# Mainboard_V1_0_HMI.net
KiCad netlist of a schematic drawn in Altium Designer
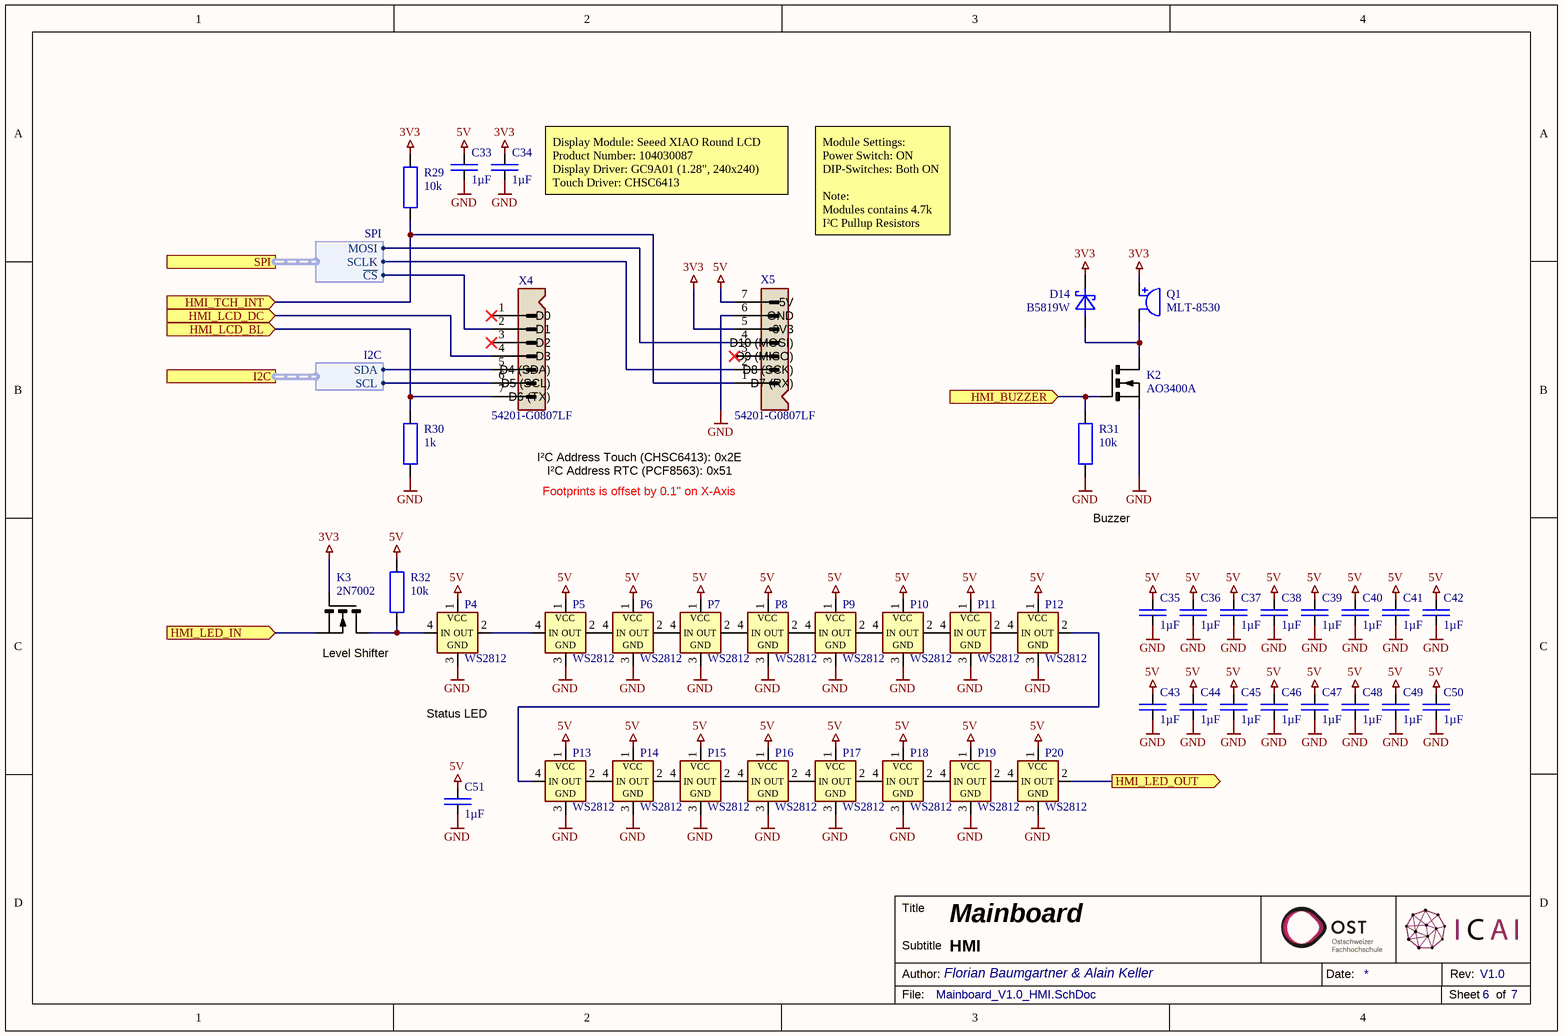
[diagram p0: Mainboard_V1.0_HMI.SchDoc]

(export (version "E")
  (design (tool "Eeschema 10.0.6"))
  (components
    (comp (ref "C33")
      (value "1µF")
      (footprint "SMD Keramikkondensator 0603")
      (description "CAP-MK")
      (libsource (lib "AudioAmp") (part "C-CAPACITOR"))
    )
    (comp (ref "C34")
      (value "1µF")
      (footprint "SMD Keramikkondensator 0603")
      (description "CAP-MK")
      (libsource (lib "AudioAmp") (part "C-CAPACITOR"))
    )
    (comp (ref "C35")
      (value "1µF")
      (footprint "SMD Keramikkondensator 0603")
      (description "CAP-MK")
      (libsource (lib "AudioAmp") (part "C-CAPACITOR"))
    )
    (comp (ref "C36")
      (value "1µF")
      (footprint "SMD Keramikkondensator 0603")
      (description "CAP-MK")
      (libsource (lib "AudioAmp") (part "C-CAPACITOR"))
    )
    (comp (ref "C37")
      (value "1µF")
      (footprint "SMD Keramikkondensator 0603")
      (description "CAP-MK")
      (libsource (lib "AudioAmp") (part "C-CAPACITOR"))
    )
    (comp (ref "C38")
      (value "1µF")
      (footprint "SMD Keramikkondensator 0603")
      (description "CAP-MK")
      (libsource (lib "AudioAmp") (part "C-CAPACITOR"))
    )
    (comp (ref "C39")
      (value "1µF")
      (footprint "SMD Keramikkondensator 0603")
      (description "CAP-MK")
      (libsource (lib "AudioAmp") (part "C-CAPACITOR"))
    )
    (comp (ref "C40")
      (value "1µF")
      (footprint "SMD Keramikkondensator 0603")
      (description "CAP-MK")
      (libsource (lib "AudioAmp") (part "C-CAPACITOR"))
    )
    (comp (ref "C41")
      (value "1µF")
      (footprint "SMD Keramikkondensator 0603")
      (description "CAP-MK")
      (libsource (lib "AudioAmp") (part "C-CAPACITOR"))
    )
    (comp (ref "C42")
      (value "1µF")
      (footprint "SMD Keramikkondensator 0603")
      (description "CAP-MK")
      (libsource (lib "AudioAmp") (part "C-CAPACITOR"))
    )
    (comp (ref "C43")
      (value "1µF")
      (footprint "SMD Keramikkondensator 0603")
      (description "CAP-MK")
      (libsource (lib "AudioAmp") (part "C-CAPACITOR"))
    )
    (comp (ref "C44")
      (value "1µF")
      (footprint "SMD Keramikkondensator 0603")
      (description "CAP-MK")
      (libsource (lib "AudioAmp") (part "C-CAPACITOR"))
    )
    (comp (ref "C45")
      (value "1µF")
      (footprint "SMD Keramikkondensator 0603")
      (description "CAP-MK")
      (libsource (lib "AudioAmp") (part "C-CAPACITOR"))
    )
    (comp (ref "C46")
      (value "1µF")
      (footprint "SMD Keramikkondensator 0603")
      (description "CAP-MK")
      (libsource (lib "AudioAmp") (part "C-CAPACITOR"))
    )
    (comp (ref "C47")
      (value "1µF")
      (footprint "SMD Keramikkondensator 0603")
      (description "CAP-MK")
      (libsource (lib "AudioAmp") (part "C-CAPACITOR"))
    )
    (comp (ref "C48")
      (value "1µF")
      (footprint "SMD Keramikkondensator 0603")
      (description "CAP-MK")
      (libsource (lib "AudioAmp") (part "C-CAPACITOR"))
    )
    (comp (ref "C49")
      (value "1µF")
      (footprint "SMD Keramikkondensator 0603")
      (description "CAP-MK")
      (libsource (lib "AudioAmp") (part "C-CAPACITOR"))
    )
    (comp (ref "C50")
      (value "1µF")
      (footprint "SMD Keramikkondensator 0603")
      (description "CAP-MK")
      (libsource (lib "AudioAmp") (part "C-CAPACITOR"))
    )
    (comp (ref "C51")
      (value "1µF")
      (footprint "SMD Keramikkondensator 0603")
      (description "CAP-MK")
      (libsource (lib "AudioAmp") (part "C-CAPACITOR"))
    )
    (comp (ref "D14")
      (value "B5819W")
      (footprint "SMD Diode SOD-123")
      (description "S-DIODE")
      (libsource (lib "TFS Integrated Library") (part "R-DIODE{colon}SCHKY"))
    )
    (comp (ref "K2")
      (value "AO3400A")
      (footprint "SMD MOSFET SOT-23")
      (description "MOSFET N-Channel")
      (libsource (lib "") (part "K-FET{colon}NIGE_1"))
    )
    (comp (ref "K3")
      (value "2N7002")
      (footprint "SMD MOSFET SOT-23")
      (description "MOSFET N-Channel")
      (libsource (lib "Nixie-Test") (part "K-FET{colon}NIGE"))
    )
    (comp (ref "P4")
      (value "WS2812")
      (footprint "SMD LED WS2812B-0807")
      (description "Smart RGB-LED")
      (libsource (lib "Acquisition-System") (part "P-WS2812B-0807"))
    )
    (comp (ref "P5")
      (value "WS2812")
      (footprint "SMD LED WS2812B-0807")
      (description "Smart RGB-LED")
      (libsource (lib "Acquisition-System") (part "P-WS2812B-0807"))
    )
    (comp (ref "P6")
      (value "WS2812")
      (footprint "SMD LED WS2812B-0807")
      (description "Smart RGB-LED")
      (libsource (lib "Acquisition-System") (part "P-WS2812B-0807"))
    )
    (comp (ref "P7")
      (value "WS2812")
      (footprint "SMD LED WS2812B-0807")
      (description "Smart RGB-LED")
      (libsource (lib "Acquisition-System") (part "P-WS2812B-0807"))
    )
    (comp (ref "P8")
      (value "WS2812")
      (footprint "SMD LED WS2812B-0807")
      (description "Smart RGB-LED")
      (libsource (lib "Acquisition-System") (part "P-WS2812B-0807"))
    )
    (comp (ref "P9")
      (value "WS2812")
      (footprint "SMD LED WS2812B-0807")
      (description "Smart RGB-LED")
      (libsource (lib "Acquisition-System") (part "P-WS2812B-0807"))
    )
    (comp (ref "P10")
      (value "WS2812")
      (footprint "SMD LED WS2812B-0807")
      (description "Smart RGB-LED")
      (libsource (lib "Acquisition-System") (part "P-WS2812B-0807"))
    )
    (comp (ref "P11")
      (value "WS2812")
      (footprint "SMD LED WS2812B-0807")
      (description "Smart RGB-LED")
      (libsource (lib "Acquisition-System") (part "P-WS2812B-0807"))
    )
    (comp (ref "P12")
      (value "WS2812")
      (footprint "SMD LED WS2812B-0807")
      (description "Smart RGB-LED")
      (libsource (lib "Acquisition-System") (part "P-WS2812B-0807"))
    )
    (comp (ref "P13")
      (value "WS2812")
      (footprint "SMD LED WS2812B-0807")
      (description "Smart RGB-LED")
      (libsource (lib "Acquisition-System") (part "P-WS2812B-0807"))
    )
    (comp (ref "P14")
      (value "WS2812")
      (footprint "SMD LED WS2812B-0807")
      (description "Smart RGB-LED")
      (libsource (lib "Acquisition-System") (part "P-WS2812B-0807"))
    )
    (comp (ref "P15")
      (value "WS2812")
      (footprint "SMD LED WS2812B-0807")
      (description "Smart RGB-LED")
      (libsource (lib "Acquisition-System") (part "P-WS2812B-0807"))
    )
    (comp (ref "P16")
      (value "WS2812")
      (footprint "SMD LED WS2812B-0807")
      (description "Smart RGB-LED")
      (libsource (lib "Acquisition-System") (part "P-WS2812B-0807"))
    )
    (comp (ref "P17")
      (value "WS2812")
      (footprint "SMD LED WS2812B-0807")
      (description "Smart RGB-LED")
      (libsource (lib "Acquisition-System") (part "P-WS2812B-0807"))
    )
    (comp (ref "P18")
      (value "WS2812")
      (footprint "SMD LED WS2812B-0807")
      (description "Smart RGB-LED")
      (libsource (lib "Acquisition-System") (part "P-WS2812B-0807"))
    )
    (comp (ref "P19")
      (value "WS2812")
      (footprint "SMD LED WS2812B-0807")
      (description "Smart RGB-LED")
      (libsource (lib "Acquisition-System") (part "P-WS2812B-0807"))
    )
    (comp (ref "P20")
      (value "WS2812")
      (footprint "SMD LED WS2812B-0807")
      (description "Smart RGB-LED")
      (libsource (lib "Acquisition-System") (part "P-WS2812B-0807"))
    )
    (comp (ref "Q1")
      (value "MLT-8530")
      (footprint "SMD Buzzer (MLT-8530)")
      (description "Electromagnetic Buzzer")
      (libsource (lib "Velotour_2022") (part "Q-Buzzer"))
    )
    (comp (ref "R29")
      (value "10k")
      (footprint "SMD Widerstand 0603")
      (description "RES (E=Heizwiderstand B=Messwandler)")
      (libsource (lib "TFS Integrated Library") (part "R-RESISTOR"))
    )
    (comp (ref "R30")
      (value "1k")
      (footprint "SMD Widerstand 0603")
      (description "RES (E=Heizwiderstand B=Messwandler)")
      (libsource (lib "TFS Integrated Library") (part "R-RESISTOR"))
    )
    (comp (ref "R31")
      (value "10k")
      (footprint "SMD Widerstand 0603")
      (description "RES (E=Heizwiderstand B=Messwandler)")
      (libsource (lib "TFS Integrated Library") (part "R-RESISTOR"))
    )
    (comp (ref "R32")
      (value "10k")
      (footprint "SMD Widerstand 0603")
      (description "RES (E=Heizwiderstand B=Messwandler)")
      (libsource (lib "TFS Integrated Library") (part "R-RESISTOR"))
    )
    (comp (ref "X4")
      (value "54201-G0807LF")
      (footprint "SMD Pin-Header 1x7")
      (libsource (lib "Mainboard") (part "X-Stiftleiste (7-Fach)"))
    )
    (comp (ref "X5")
      (value "54201-G0807LF")
      (footprint "SMD Pin-Header 1x7")
      (libsource (lib "") (part "X-Stiftleiste (7-Fach)_1"))
    )
  )
  (nets
    (net (code "3") (name "/HMI_BUZZER") (class "Default")
      (node (ref "K2") (pin "G") (pinfunction "G_G") (pintype "passive"))
      (node (ref "R31") (pin "2") (pinfunction "2_2") (pintype "passive"))
    )
    (net (code "4") (name "/HMI_LCD_BL") (class "Default")
      (node (ref "R30") (pin "2") (pinfunction "2_2") (pintype "passive"))
      (node (ref "X4") (pin "7") (pinfunction "7_7") (pintype "passive"))
    )
    (net (code "5") (name "/HMI_LCD_DC") (class "Default")
      (node (ref "X4") (pin "4") (pinfunction "4_4") (pintype "passive"))
    )
    (net (code "6") (name "/HMI_LED_IN") (class "Default")
      (node (ref "K3") (pin "S") (pinfunction "S_S") (pintype "passive"))
    )
    (net (code "7") (name "/HMI_LED_OUT") (class "Default")
      (node (ref "P20") (pin "2") (pinfunction "OUT_2") (pintype "passive"))
    )
    (net (code "8") (name "/HMI_TCH_INT") (class "Default")
      (node (ref "R29") (pin "1") (pinfunction "1_1") (pintype "passive"))
      (node (ref "X5") (pin "1") (pinfunction "1_1") (pintype "passive"))
    )
    (net (code "9") (name "/MOSI") (class "Default")
      (node (ref "X5") (pin "4") (pinfunction "4_4") (pintype "passive"))
    )
    (net (code "10") (name "/SCL") (class "Default")
      (node (ref "X4") (pin "6") (pinfunction "6_6") (pintype "passive"))
    )
    (net (code "11") (name "/SCLK") (class "Default")
      (node (ref "X5") (pin "2") (pinfunction "2_2") (pintype "passive"))
    )
    (net (code "12") (name "/SDA") (class "Default")
      (node (ref "X4") (pin "5") (pinfunction "5_5") (pintype "passive"))
    )
    (net (code "15") (name "/~{CS}") (class "Default")
      (node (ref "X4") (pin "2") (pinfunction "2_2") (pintype "passive"))
    )
    (net (code "16") (name "3V3") (class "Default")
      (node (ref "C34") (pin "2") (pinfunction "2_2") (pintype "passive"))
      (node (ref "D14") (pin "K") (pinfunction "K_K") (pintype "passive"))
      (node (ref "K3") (pin "G") (pinfunction "G_G") (pintype "passive"))
      (node (ref "Q1") (pin "1") (pinfunction "P_1") (pintype "power_in"))
      (node (ref "R29") (pin "2") (pinfunction "2_2") (pintype "passive"))
      (node (ref "X5") (pin "5") (pinfunction "5_5") (pintype "passive"))
    )
    (net (code "17") (name "5V") (class "Default")
      (node (ref "C33") (pin "2") (pinfunction "2_2") (pintype "passive"))
      (node (ref "C35") (pin "2") (pinfunction "2_2") (pintype "passive"))
      (node (ref "C36") (pin "2") (pinfunction "2_2") (pintype "passive"))
      (node (ref "C37") (pin "2") (pinfunction "2_2") (pintype "passive"))
      (node (ref "C38") (pin "2") (pinfunction "2_2") (pintype "passive"))
      (node (ref "C39") (pin "2") (pinfunction "2_2") (pintype "passive"))
      (node (ref "C40") (pin "2") (pinfunction "2_2") (pintype "passive"))
      (node (ref "C41") (pin "2") (pinfunction "2_2") (pintype "passive"))
      (node (ref "C42") (pin "2") (pinfunction "2_2") (pintype "passive"))
      (node (ref "C43") (pin "2") (pinfunction "2_2") (pintype "passive"))
      (node (ref "C44") (pin "2") (pinfunction "2_2") (pintype "passive"))
      (node (ref "C45") (pin "2") (pinfunction "2_2") (pintype "passive"))
      (node (ref "C46") (pin "2") (pinfunction "2_2") (pintype "passive"))
      (node (ref "C47") (pin "2") (pinfunction "2_2") (pintype "passive"))
      (node (ref "C48") (pin "2") (pinfunction "2_2") (pintype "passive"))
      (node (ref "C49") (pin "2") (pinfunction "2_2") (pintype "passive"))
      (node (ref "C50") (pin "2") (pinfunction "2_2") (pintype "passive"))
      (node (ref "C51") (pin "2") (pinfunction "2_2") (pintype "passive"))
      (node (ref "P10") (pin "1") (pinfunction "VCC_1") (pintype "power_in"))
      (node (ref "P11") (pin "1") (pinfunction "VCC_1") (pintype "power_in"))
      (node (ref "P12") (pin "1") (pinfunction "VCC_1") (pintype "power_in"))
      (node (ref "P13") (pin "1") (pinfunction "VCC_1") (pintype "power_in"))
      (node (ref "P14") (pin "1") (pinfunction "VCC_1") (pintype "power_in"))
      (node (ref "P15") (pin "1") (pinfunction "VCC_1") (pintype "power_in"))
      (node (ref "P16") (pin "1") (pinfunction "VCC_1") (pintype "power_in"))
      (node (ref "P17") (pin "1") (pinfunction "VCC_1") (pintype "power_in"))
      (node (ref "P18") (pin "1") (pinfunction "VCC_1") (pintype "power_in"))
      (node (ref "P19") (pin "1") (pinfunction "VCC_1") (pintype "power_in"))
      (node (ref "P20") (pin "1") (pinfunction "VCC_1") (pintype "power_in"))
      (node (ref "P4") (pin "1") (pinfunction "VCC_1") (pintype "power_in"))
      (node (ref "P5") (pin "1") (pinfunction "VCC_1") (pintype "power_in"))
      (node (ref "P6") (pin "1") (pinfunction "VCC_1") (pintype "power_in"))
      (node (ref "P7") (pin "1") (pinfunction "VCC_1") (pintype "power_in"))
      (node (ref "P8") (pin "1") (pinfunction "VCC_1") (pintype "power_in"))
      (node (ref "P9") (pin "1") (pinfunction "VCC_1") (pintype "power_in"))
      (node (ref "R32") (pin "2") (pinfunction "2_2") (pintype "passive"))
      (node (ref "X5") (pin "7") (pinfunction "7_7") (pintype "passive"))
    )
    (net (code "18") (name "GND") (class "Default")
      (node (ref "C33") (pin "1") (pinfunction "1_1") (pintype "passive"))
      (node (ref "C34") (pin "1") (pinfunction "1_1") (pintype "passive"))
      (node (ref "C35") (pin "1") (pinfunction "1_1") (pintype "passive"))
      (node (ref "C36") (pin "1") (pinfunction "1_1") (pintype "passive"))
      (node (ref "C37") (pin "1") (pinfunction "1_1") (pintype "passive"))
      (node (ref "C38") (pin "1") (pinfunction "1_1") (pintype "passive"))
      (node (ref "C39") (pin "1") (pinfunction "1_1") (pintype "passive"))
      (node (ref "C40") (pin "1") (pinfunction "1_1") (pintype "passive"))
      (node (ref "C41") (pin "1") (pinfunction "1_1") (pintype "passive"))
      (node (ref "C42") (pin "1") (pinfunction "1_1") (pintype "passive"))
      (node (ref "C43") (pin "1") (pinfunction "1_1") (pintype "passive"))
      (node (ref "C44") (pin "1") (pinfunction "1_1") (pintype "passive"))
      (node (ref "C45") (pin "1") (pinfunction "1_1") (pintype "passive"))
      (node (ref "C46") (pin "1") (pinfunction "1_1") (pintype "passive"))
      (node (ref "C47") (pin "1") (pinfunction "1_1") (pintype "passive"))
      (node (ref "C48") (pin "1") (pinfunction "1_1") (pintype "passive"))
      (node (ref "C49") (pin "1") (pinfunction "1_1") (pintype "passive"))
      (node (ref "C50") (pin "1") (pinfunction "1_1") (pintype "passive"))
      (node (ref "C51") (pin "1") (pinfunction "1_1") (pintype "passive"))
      (node (ref "K2") (pin "S") (pinfunction "S_S") (pintype "passive"))
      (node (ref "P10") (pin "3") (pinfunction "GND_3") (pintype "power_in"))
      (node (ref "P11") (pin "3") (pinfunction "GND_3") (pintype "power_in"))
      (node (ref "P12") (pin "3") (pinfunction "GND_3") (pintype "power_in"))
      (node (ref "P13") (pin "3") (pinfunction "GND_3") (pintype "power_in"))
      (node (ref "P14") (pin "3") (pinfunction "GND_3") (pintype "power_in"))
      (node (ref "P15") (pin "3") (pinfunction "GND_3") (pintype "power_in"))
      (node (ref "P16") (pin "3") (pinfunction "GND_3") (pintype "power_in"))
      (node (ref "P17") (pin "3") (pinfunction "GND_3") (pintype "power_in"))
      (node (ref "P18") (pin "3") (pinfunction "GND_3") (pintype "power_in"))
      (node (ref "P19") (pin "3") (pinfunction "GND_3") (pintype "power_in"))
      (node (ref "P20") (pin "3") (pinfunction "GND_3") (pintype "power_in"))
      (node (ref "P4") (pin "3") (pinfunction "GND_3") (pintype "power_in"))
      (node (ref "P5") (pin "3") (pinfunction "GND_3") (pintype "power_in"))
      (node (ref "P6") (pin "3") (pinfunction "GND_3") (pintype "power_in"))
      (node (ref "P7") (pin "3") (pinfunction "GND_3") (pintype "power_in"))
      (node (ref "P8") (pin "3") (pinfunction "GND_3") (pintype "power_in"))
      (node (ref "P9") (pin "3") (pinfunction "GND_3") (pintype "power_in"))
      (node (ref "R30") (pin "1") (pinfunction "1_1") (pintype "passive"))
      (node (ref "R31") (pin "1") (pinfunction "1_1") (pintype "passive"))
      (node (ref "X5") (pin "6") (pinfunction "6_6") (pintype "passive"))
    )
    (net (code "19") (name "Net-(P4-IN)") (class "Default")
      (node (ref "K3") (pin "D") (pinfunction "D_D") (pintype "passive"))
      (node (ref "P4") (pin "4") (pinfunction "IN_4") (pintype "passive"))
      (node (ref "R32") (pin "1") (pinfunction "1_1") (pintype "passive"))
    )
    (net (code "20") (name "Net-(P4-OUT)") (class "Default")
      (node (ref "P4") (pin "2") (pinfunction "OUT_2") (pintype "passive"))
      (node (ref "P5") (pin "4") (pinfunction "IN_4") (pintype "passive"))
    )
    (net (code "21") (name "Net-(P5-OUT)") (class "Default")
      (node (ref "P5") (pin "2") (pinfunction "OUT_2") (pintype "passive"))
      (node (ref "P6") (pin "4") (pinfunction "IN_4") (pintype "passive"))
    )
    (net (code "22") (name "Net-(P6-OUT)") (class "Default")
      (node (ref "P6") (pin "2") (pinfunction "OUT_2") (pintype "passive"))
      (node (ref "P7") (pin "4") (pinfunction "IN_4") (pintype "passive"))
    )
    (net (code "23") (name "Net-(P7-OUT)") (class "Default")
      (node (ref "P7") (pin "2") (pinfunction "OUT_2") (pintype "passive"))
      (node (ref "P8") (pin "4") (pinfunction "IN_4") (pintype "passive"))
    )
    (net (code "24") (name "Net-(P8-OUT)") (class "Default")
      (node (ref "P8") (pin "2") (pinfunction "OUT_2") (pintype "passive"))
      (node (ref "P9") (pin "4") (pinfunction "IN_4") (pintype "passive"))
    )
    (net (code "25") (name "Net-(P10-IN)") (class "Default")
      (node (ref "P10") (pin "4") (pinfunction "IN_4") (pintype "passive"))
      (node (ref "P9") (pin "2") (pinfunction "OUT_2") (pintype "passive"))
    )
    (net (code "26") (name "Net-(P10-OUT)") (class "Default")
      (node (ref "P10") (pin "2") (pinfunction "OUT_2") (pintype "passive"))
      (node (ref "P11") (pin "4") (pinfunction "IN_4") (pintype "passive"))
    )
    (net (code "27") (name "Net-(P11-OUT)") (class "Default")
      (node (ref "P11") (pin "2") (pinfunction "OUT_2") (pintype "passive"))
      (node (ref "P12") (pin "4") (pinfunction "IN_4") (pintype "passive"))
    )
    (net (code "28") (name "Net-(P12-OUT)") (class "Default")
      (node (ref "P12") (pin "2") (pinfunction "OUT_2") (pintype "passive"))
      (node (ref "P13") (pin "4") (pinfunction "IN_4") (pintype "passive"))
    )
    (net (code "29") (name "Net-(P13-OUT)") (class "Default")
      (node (ref "P13") (pin "2") (pinfunction "OUT_2") (pintype "passive"))
      (node (ref "P14") (pin "4") (pinfunction "IN_4") (pintype "passive"))
    )
    (net (code "30") (name "Net-(P14-OUT)") (class "Default")
      (node (ref "P14") (pin "2") (pinfunction "OUT_2") (pintype "passive"))
      (node (ref "P15") (pin "4") (pinfunction "IN_4") (pintype "passive"))
    )
    (net (code "31") (name "Net-(P15-OUT)") (class "Default")
      (node (ref "P15") (pin "2") (pinfunction "OUT_2") (pintype "passive"))
      (node (ref "P16") (pin "4") (pinfunction "IN_4") (pintype "passive"))
    )
    (net (code "32") (name "Net-(P16-OUT)") (class "Default")
      (node (ref "P16") (pin "2") (pinfunction "OUT_2") (pintype "passive"))
      (node (ref "P17") (pin "4") (pinfunction "IN_4") (pintype "passive"))
    )
    (net (code "33") (name "Net-(P17-OUT)") (class "Default")
      (node (ref "P17") (pin "2") (pinfunction "OUT_2") (pintype "passive"))
      (node (ref "P18") (pin "4") (pinfunction "IN_4") (pintype "passive"))
    )
    (net (code "34") (name "Net-(P18-OUT)") (class "Default")
      (node (ref "P18") (pin "2") (pinfunction "OUT_2") (pintype "passive"))
      (node (ref "P19") (pin "4") (pinfunction "IN_4") (pintype "passive"))
    )
    (net (code "35") (name "Net-(P19-OUT)") (class "Default")
      (node (ref "P19") (pin "2") (pinfunction "OUT_2") (pintype "passive"))
      (node (ref "P20") (pin "4") (pinfunction "IN_4") (pintype "passive"))
    )
    (net (code "36") (name "Net-(Q1-M)") (class "Default")
      (node (ref "D14") (pin "A") (pinfunction "A_A") (pintype "passive"))
      (node (ref "K2") (pin "D") (pinfunction "D_D") (pintype "passive"))
      (node (ref "Q1") (pin "2") (pinfunction "M_2") (pintype "power_in"))
    )
    (net (code "37") (name "unconnected-(X4-Pad1)") (class "Default")
      (node (ref "X4") (pin "1") (pinfunction "1_1") (pintype "passive+no_connect"))
    )
    (net (code "38") (name "unconnected-(X4-Pad3)") (class "Default")
      (node (ref "X4") (pin "3") (pinfunction "3_3") (pintype "passive+no_connect"))
    )
    (net (code "39") (name "unconnected-(X5-Pad3)") (class "Default")
      (node (ref "X5") (pin "3") (pinfunction "3_3") (pintype "passive+no_connect"))
    )
  )
)
